# Crossover_LP.net
KiCad netlist of a schematic drawn in EAGLE
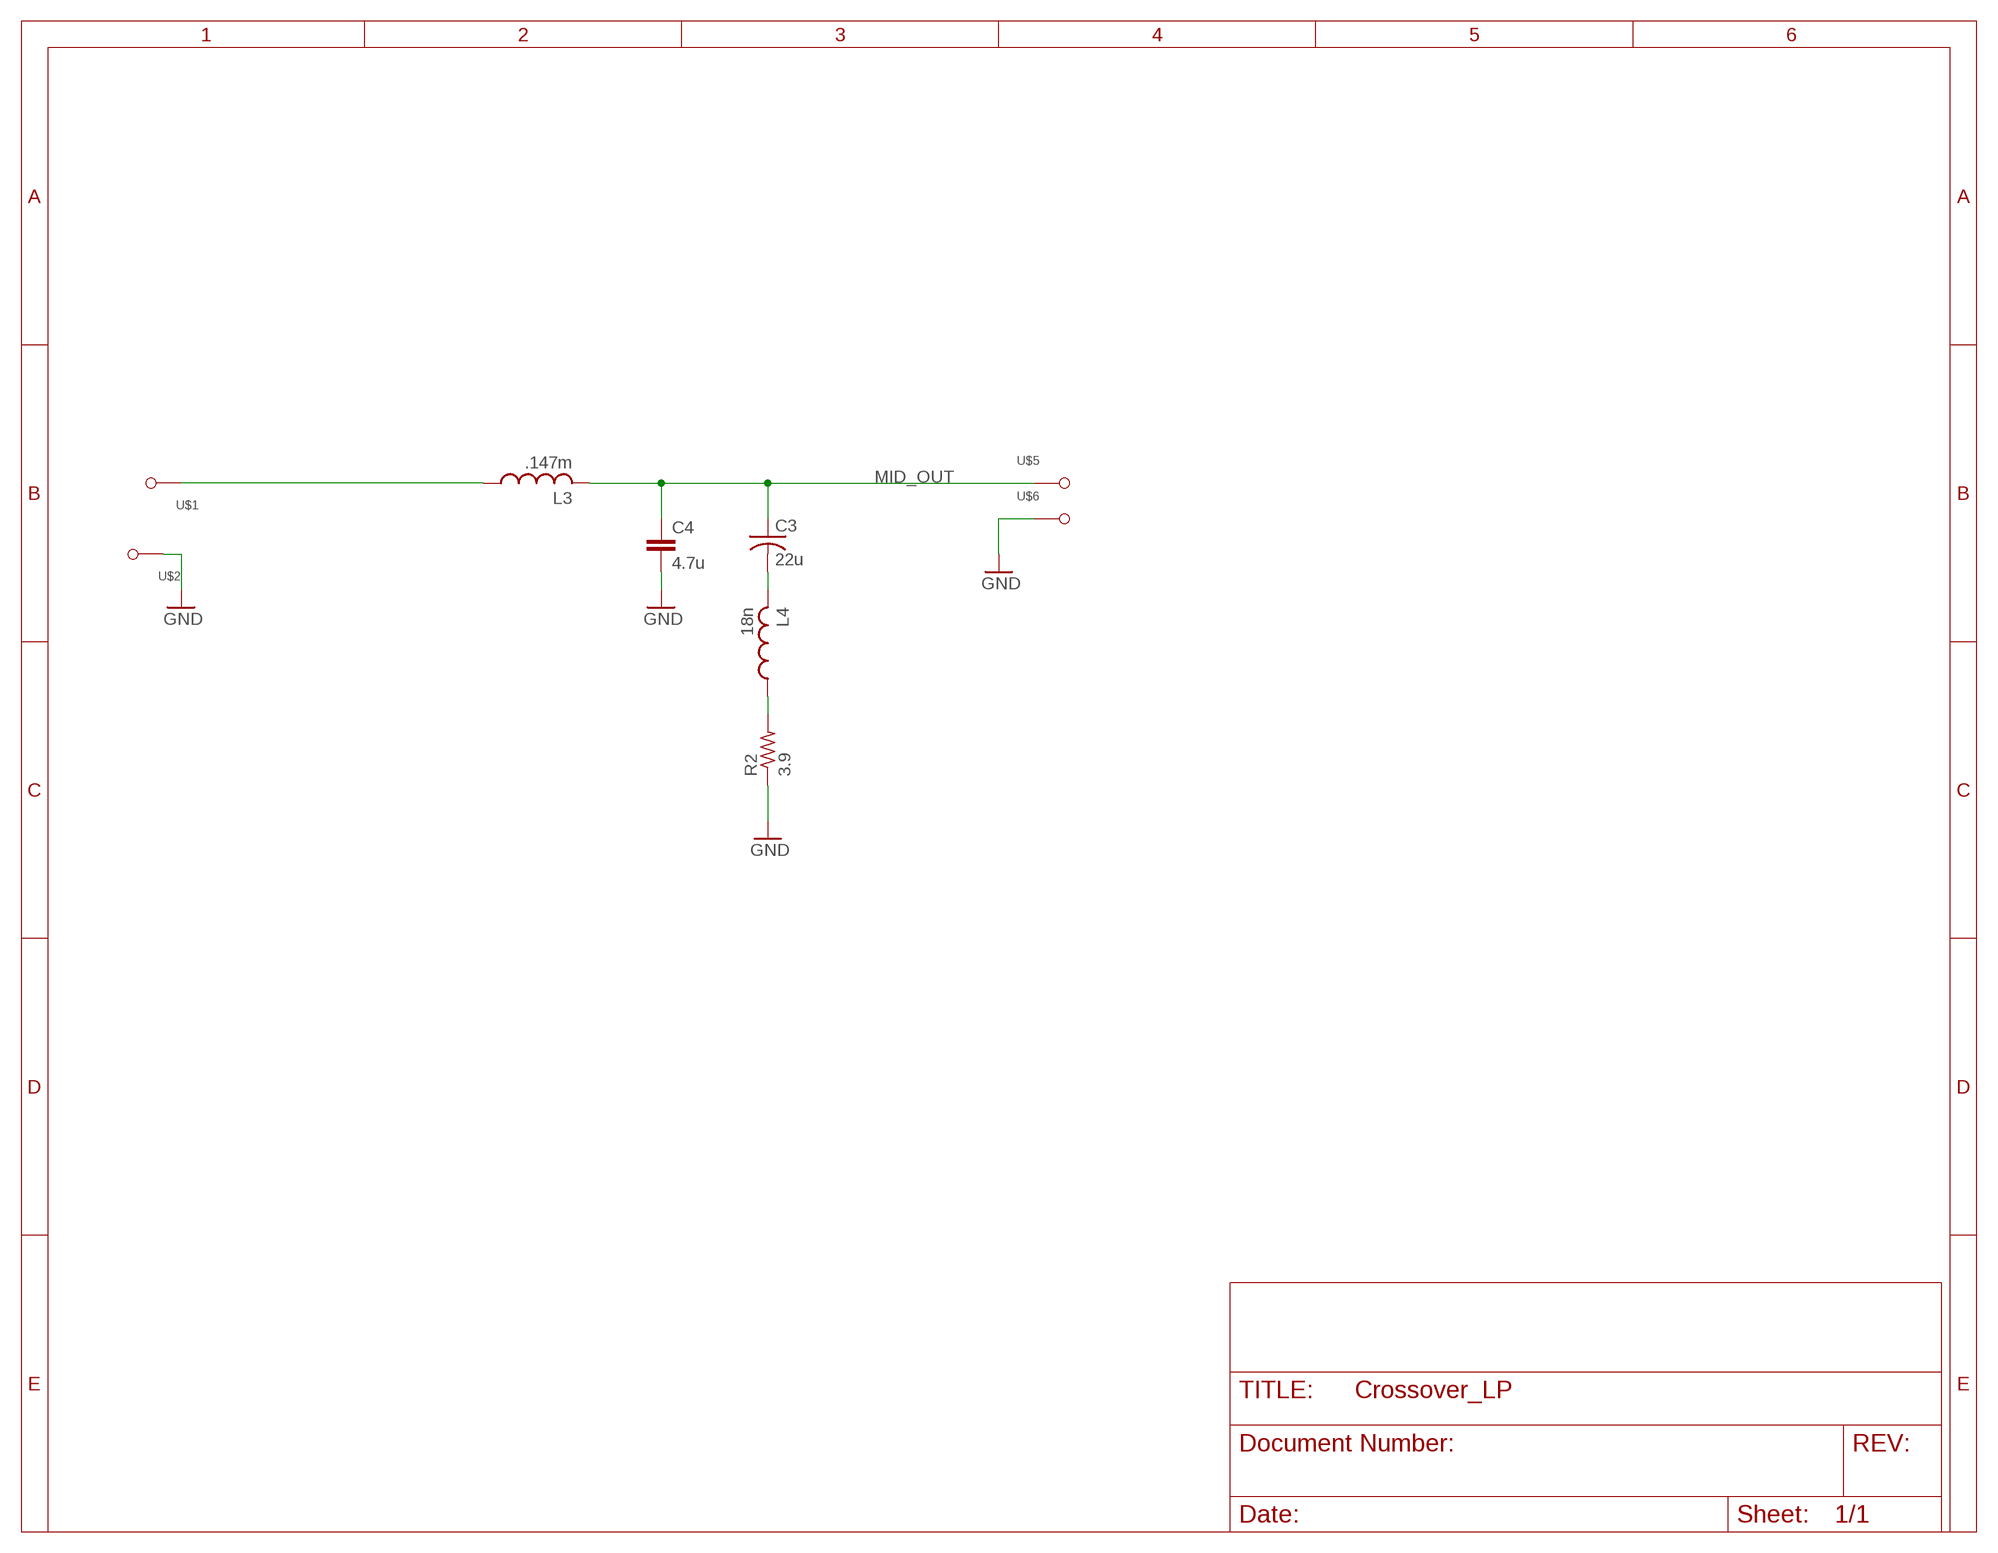
[diagram p0: schematic, sheet 1]

(export (version "E")
  (design (tool "Eeschema 10.0.6"))
  (components
    (comp (ref "C3")
      (value "22u")
      (footprint "eagle-import:5MMP_10MMD")
      (libsource (lib "eagle-import") (part "C-USC5MMP_10MMD"))
    )
    (comp (ref "C4")
      (value "4.7u")
      (footprint "eagle-import:C225-074X268")
      (libsource (lib "eagle-import") (part "C-EU225-074X268"))
    )
    (comp (ref "L3")
      (value ".147m")
      (footprint "eagle-import:AIR_COIL_2INX3_4IN")
      (libsource (lib "eagle-import") (part "L-US"))
    )
    (comp (ref "L4")
      (value "18n")
      (footprint "eagle-import:AIR_COIL_2INX3_4IN")
      (libsource (lib "eagle-import") (part "L-US"))
    )
    (comp (ref "R2")
      (value "3.9")
      (footprint "eagle-import:9.5MMX9MMX22MM")
      (libsource (lib "eagle-import") (part "R-US_5W"))
    )
    (comp (ref "U$1")
      (value "18AWG_HOLE")
      (footprint "eagle-import:18AWG_HOLE")
      (libsource (lib "eagle-import") (part "18AWG_HOLE"))
    )
    (comp (ref "U$2")
      (value "18AWG_HOLE")
      (footprint "eagle-import:18AWG_HOLE")
      (libsource (lib "eagle-import") (part "18AWG_HOLE"))
    )
    (comp (ref "U$5")
      (value "18AWG_HOLE")
      (footprint "eagle-import:18AWG_HOLE")
      (libsource (lib "eagle-import") (part "18AWG_HOLE"))
    )
    (comp (ref "U$6")
      (value "18AWG_HOLE")
      (footprint "eagle-import:18AWG_HOLE")
      (libsource (lib "eagle-import") (part "18AWG_HOLE"))
    )
  )
  (nets
    (net (code "1") (name "/MID_OUT") (class "Default")
      (node (ref "C3") (pin "POS") (pinfunction "1_POS") (pintype "passive"))
      (node (ref "C4") (pin "1") (pinfunction "1_1") (pintype "passive"))
      (node (ref "L3") (pin "P$2") (pinfunction "2_P$2") (pintype "passive"))
      (node (ref "U$5") (pin "P$1") (pinfunction ">NAME_P$1") (pintype "passive"))
    )
    (net (code "2") (name "GND") (class "Default")
      (node (ref "C4") (pin "2") (pinfunction "2_2") (pintype "passive"))
      (node (ref "R2") (pin "P$1") (pinfunction "1_P$1") (pintype "passive"))
      (node (ref "U$2") (pin "P$1") (pinfunction ">NAME_P$1") (pintype "passive"))
      (node (ref "U$6") (pin "P$1") (pinfunction ">NAME_P$1") (pintype "passive"))
    )
    (net (code "3") (name "Net-(C3-2)") (class "Default")
      (node (ref "C3") (pin "NEG") (pinfunction "2_NEG") (pintype "passive"))
      (node (ref "L4") (pin "P$2") (pinfunction "2_P$2") (pintype "passive"))
    )
    (net (code "4") (name "Net-(L3-1)") (class "Default")
      (node (ref "L3") (pin "P$1") (pinfunction "1_P$1") (pintype "passive"))
      (node (ref "U$1") (pin "P$1") (pinfunction ">NAME_P$1") (pintype "passive"))
    )
    (net (code "5") (name "Net-(L4-1)") (class "Default")
      (node (ref "L4") (pin "P$1") (pinfunction "1_P$1") (pintype "passive"))
      (node (ref "R2") (pin "P$2") (pinfunction "2_P$2") (pintype "passive"))
    )
  )
)
